# MolunSmartHomeLights_2021-06-01.net
KiCad netlist of a schematic drawn in EasyEDA
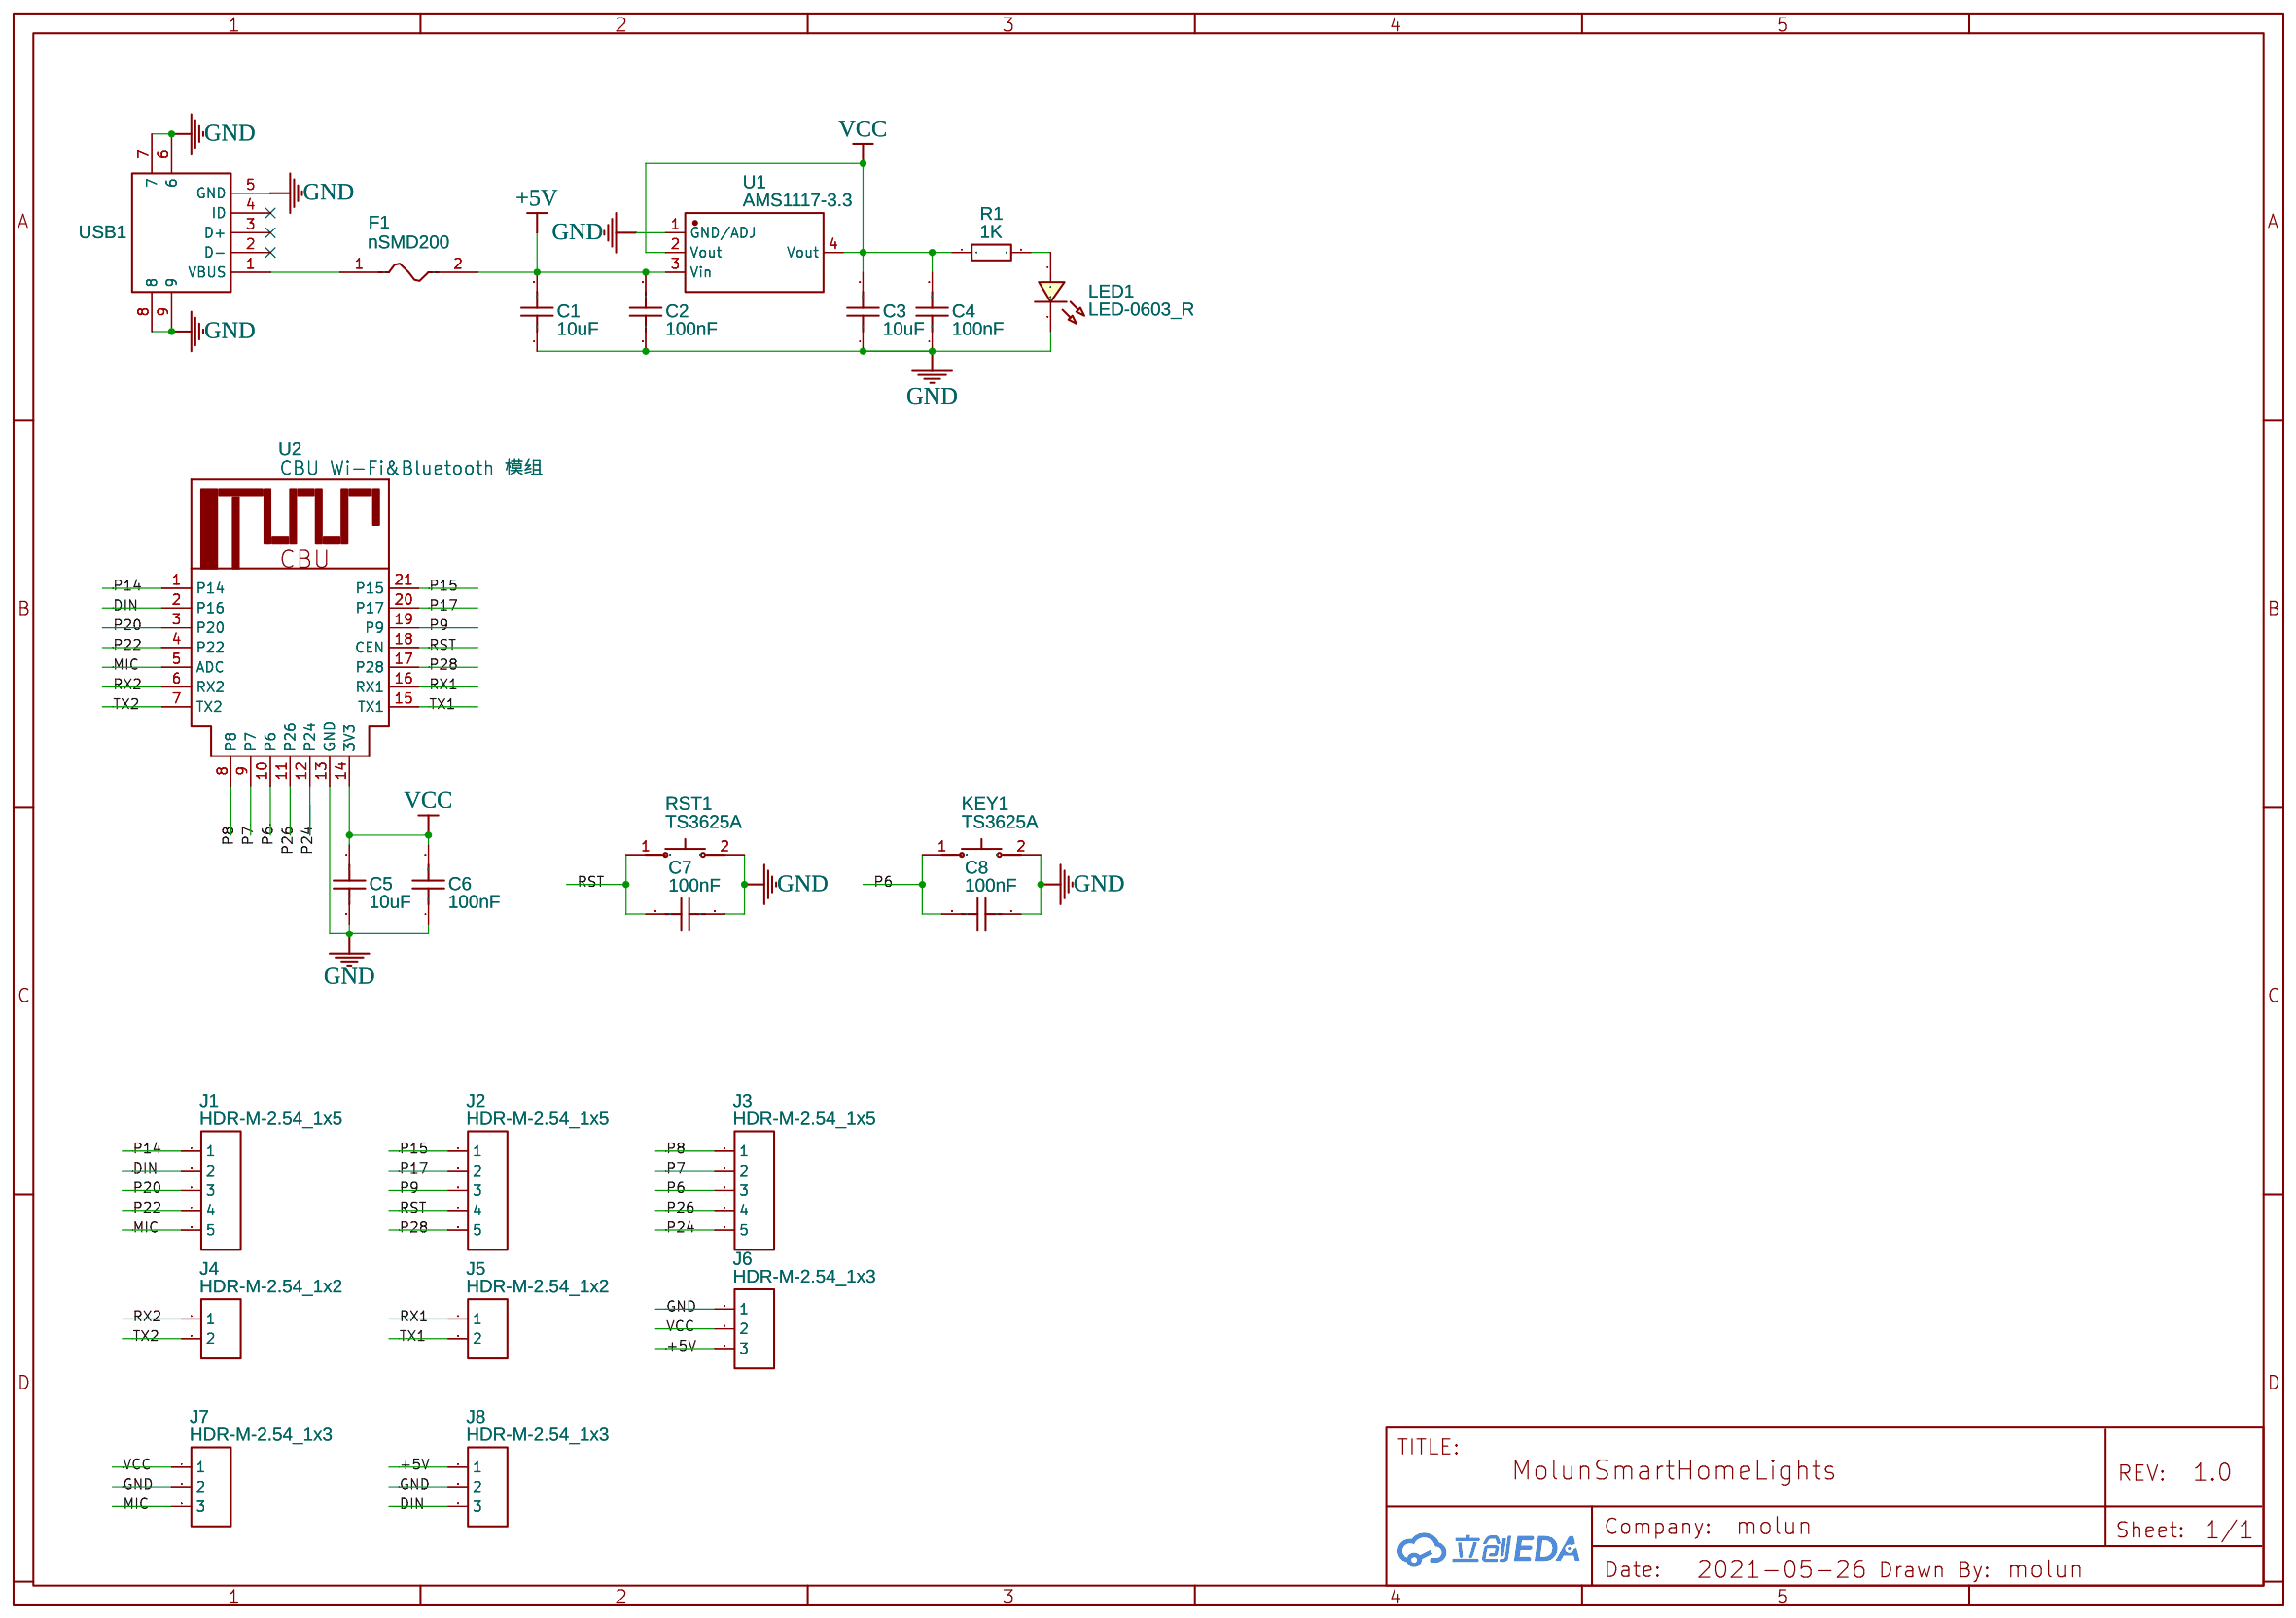
[diagram p0: MolunSmartHomeLights]
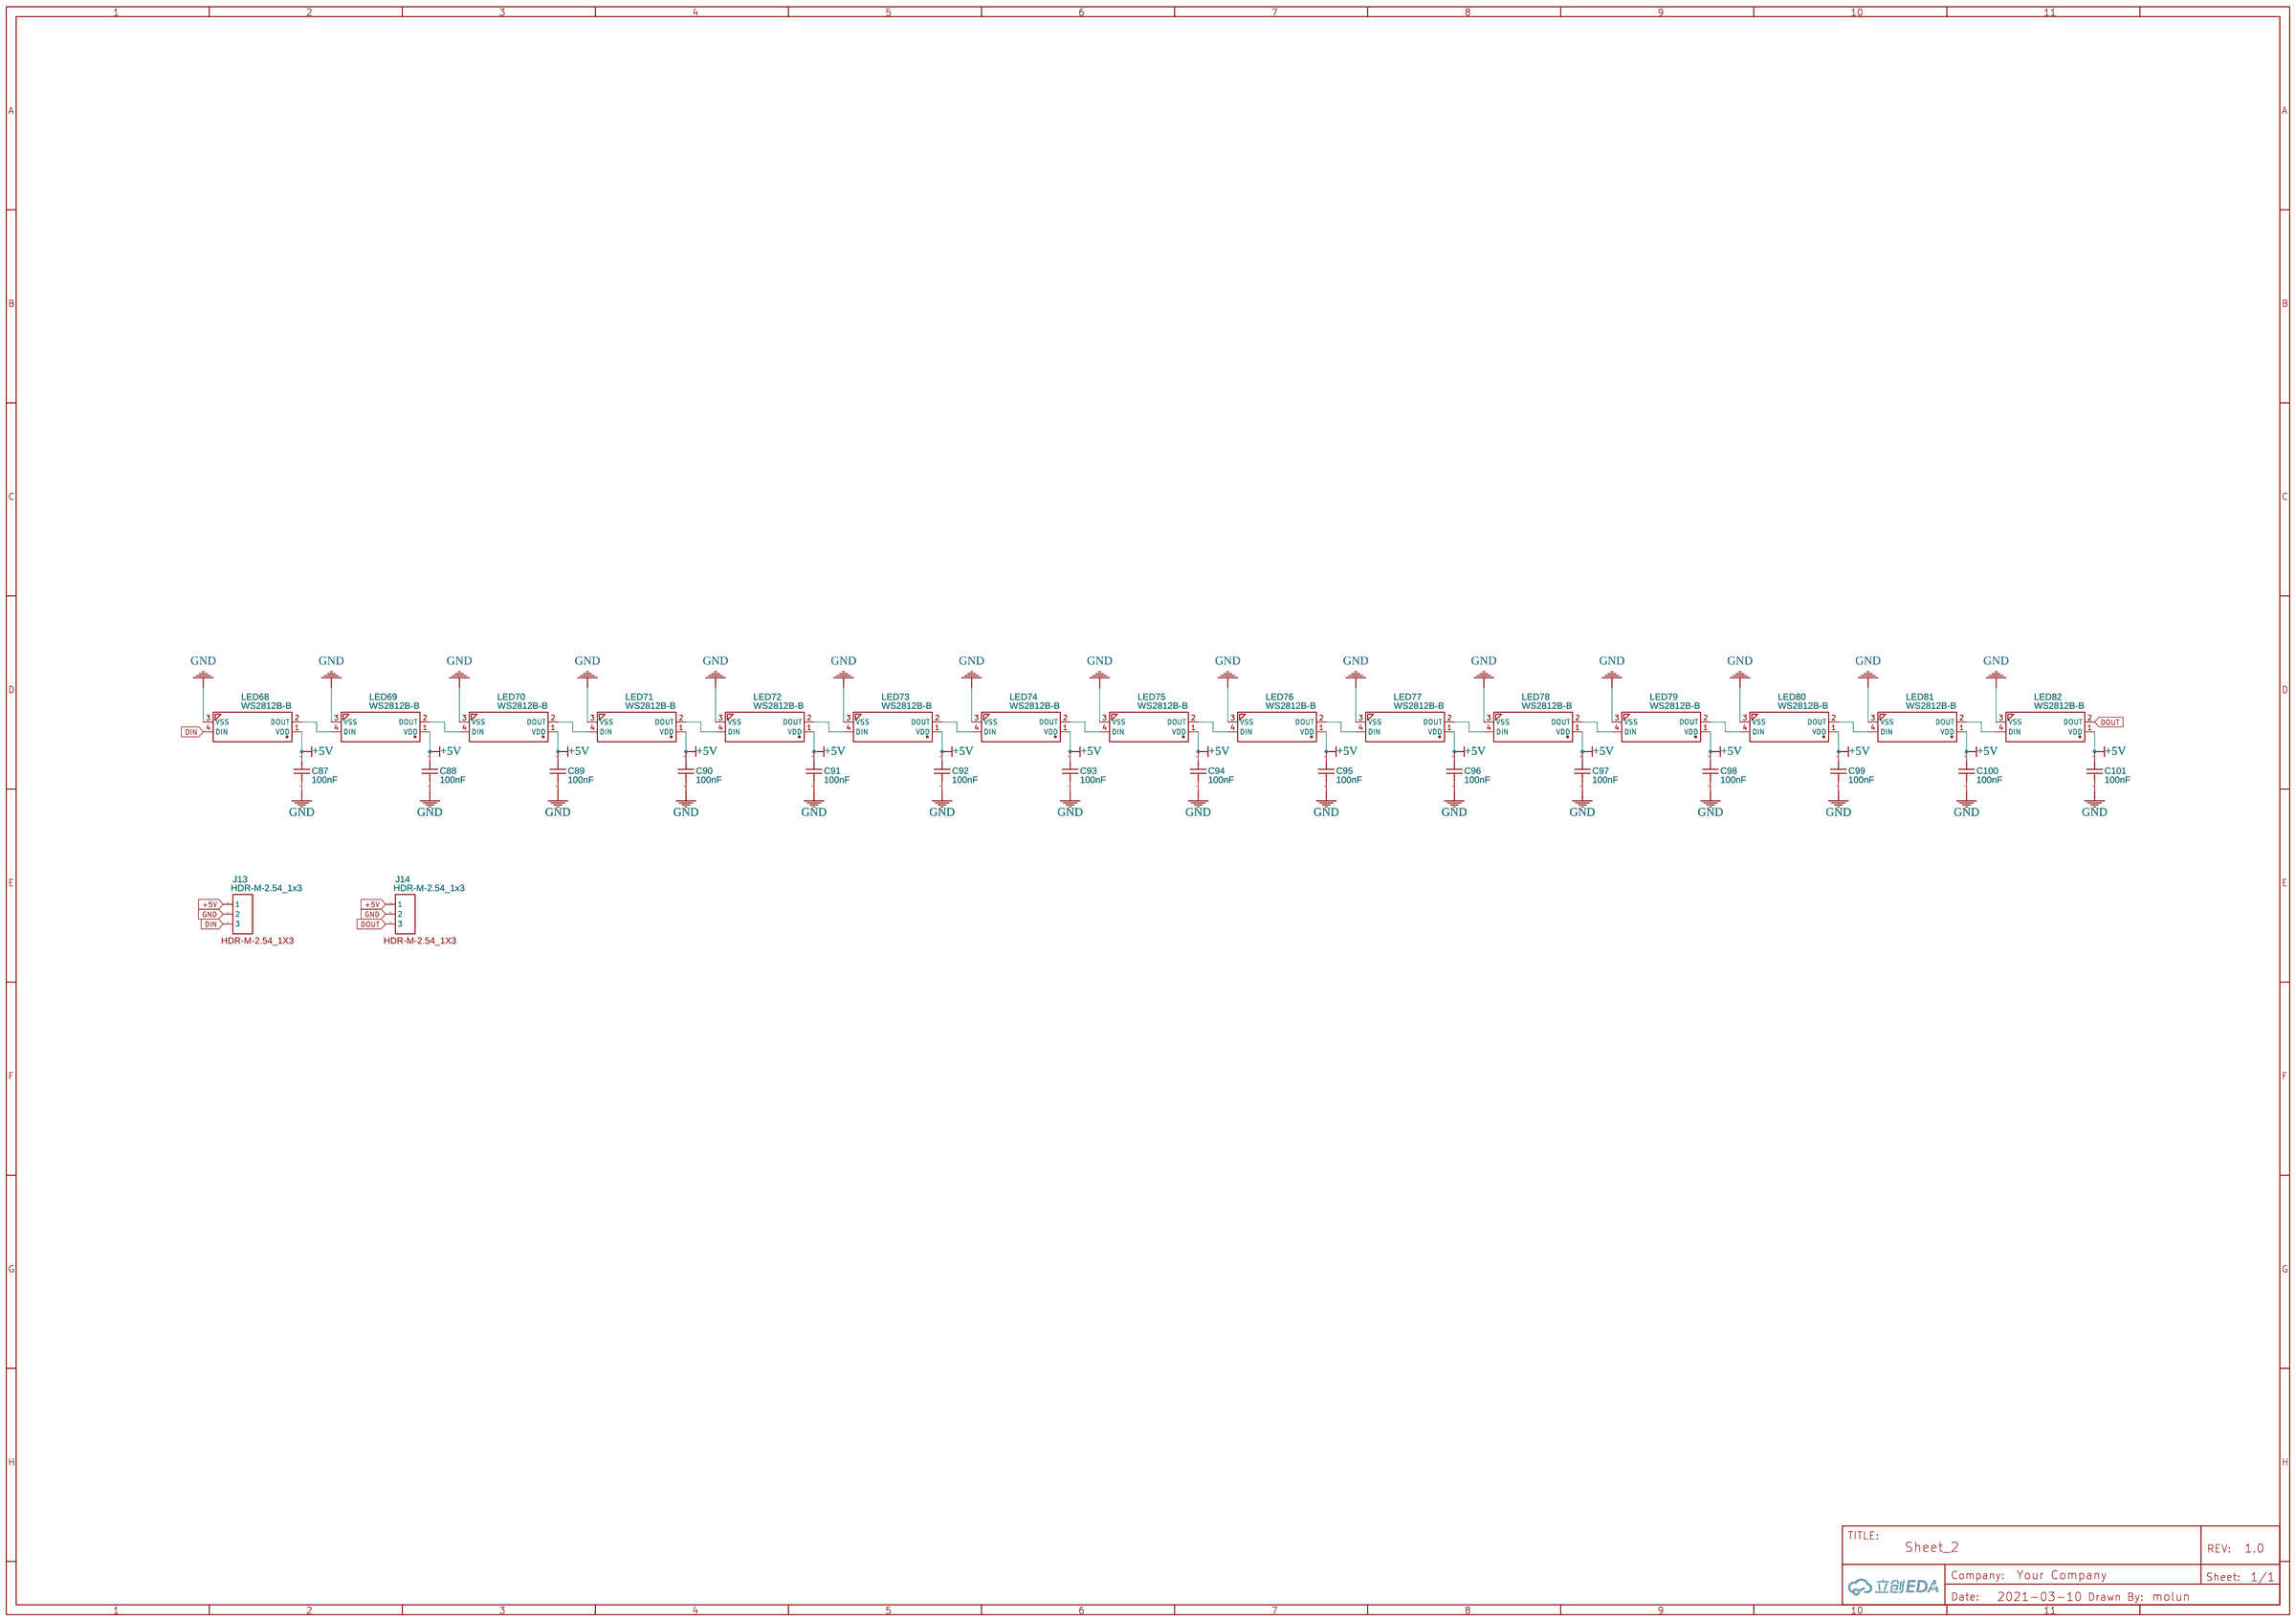
[diagram p1: 4合1 WS2812B圆环灯板]

(export (version "E")
  (design (tool "Eeschema 10.0.6"))
  (components
    (comp (ref "C1")
      (value "10uF")
      (fields
        (field (name "BOM_Manufacturer Part") "CC0603KRX5R6BB106")
        (field (name "BOM_Supplier Part") "C326057")
      )
      (libsource (lib "") (part "CC0603KRX5R6BB106"))
    )
    (comp (ref "C2")
      (value "100nF")
      (fields
        (field (name "BOM_Manufacturer Part") "AC0603KRX7R9BB104")
        (field (name "BOM_Supplier Part") "C149620")
      )
      (libsource (lib "") (part "AC0603KRX7R9BB104"))
    )
    (comp (ref "C3")
      (value "10uF")
      (fields
        (field (name "BOM_Manufacturer Part") "CC0603KRX5R6BB106")
        (field (name "BOM_Supplier Part") "C326057")
      )
      (libsource (lib "") (part "CC0603KRX5R6BB106"))
    )
    (comp (ref "C4")
      (value "100nF")
      (fields
        (field (name "BOM_Manufacturer Part") "AC0603KRX7R9BB104")
        (field (name "BOM_Supplier Part") "C149620")
      )
      (libsource (lib "") (part "AC0603KRX7R9BB104"))
    )
    (comp (ref "C5")
      (value "10uF")
      (fields
        (field (name "BOM_Manufacturer Part") "CL10A106MQ8NNNC")
        (field (name "BOM_Supplier Part") "C1691")
      )
      (libsource (lib "") (part "CL10A106MQ8NNNC"))
    )
    (comp (ref "C6")
      (value "100nF")
      (fields
        (field (name "BOM_Manufacturer Part") "CC0603KRX7R7BB104")
        (field (name "BOM_Supplier Part") "C108079")
      )
      (libsource (lib "") (part "CC0603KRX7R7BB104_1"))
    )
    (comp (ref "C7")
      (value "100nF")
      (fields
        (field (name "BOM_Manufacturer Part") "CC0603KRX7R7BB104")
        (field (name "BOM_Supplier Part") "C108079")
      )
      (libsource (lib "") (part "CC0603KRX7R7BB104"))
    )
    (comp (ref "C8")
      (value "100nF")
      (fields
        (field (name "BOM_Manufacturer Part") "CC0603KRX7R7BB104")
        (field (name "BOM_Supplier Part") "C108079")
      )
      (libsource (lib "") (part "CC0603KRX7R7BB104"))
    )
    (comp (ref "F1")
      (value "nSMD200")
      (fields (field (name "BOM_Supplier Part") "C70085"))
      (libsource (lib "") (part "nSMD200"))
    )
    (comp (ref "J1")
      (value "HDR-M-2.54_1x5")
      (fields (field (name "BOM_Supplier Part") "C358687"))
      (libsource (lib "") (part "HDR-M-2.54_1x5"))
    )
    (comp (ref "J2")
      (value "HDR-M-2.54_1x5")
      (fields (field (name "BOM_Supplier Part") "C358687"))
      (libsource (lib "") (part "HDR-M-2.54_1x5"))
    )
    (comp (ref "J3")
      (value "HDR-M-2.54_1x5")
      (fields (field (name "BOM_Supplier Part") "C358687"))
      (libsource (lib "") (part "HDR-M-2.54_1x5"))
    )
    (comp (ref "J4")
      (value "HDR-M-2.54_1x2")
      (fields (field (name "BOM_Supplier Part") "C124375"))
      (libsource (lib "") (part "HDR-M-2.54_1x2"))
    )
    (comp (ref "J5")
      (value "HDR-M-2.54_1x2")
      (fields (field (name "BOM_Supplier Part") "C124375"))
      (libsource (lib "") (part "HDR-M-2.54_1x2"))
    )
    (comp (ref "J6")
      (value "HDR-M-2.54_1x3")
      (fields (field (name "BOM_Supplier Part") "C180248"))
      (libsource (lib "") (part "HDR-M-2.54_1x3"))
    )
    (comp (ref "J7")
      (value "HDR-M-2.54_1x3")
      (fields (field (name "BOM_Supplier Part") "C180248"))
      (libsource (lib "") (part "HDR-M-2.54_1x3"))
    )
    (comp (ref "J8")
      (value "HDR-M-2.54_1x3")
      (fields (field (name "BOM_Supplier Part") "C180248"))
      (libsource (lib "") (part "HDR-M-2.54_1x3"))
    )
    (comp (ref "KEY1")
      (value "TS3625A")
      (fields (field (name "BOM_Supplier Part") "C398053"))
      (libsource (lib "") (part "TS3625A"))
    )
    (comp (ref "LED1")
      (value "LED-0603_R")
      (fields
        (field (name "BOM_Manufacturer Part") "19-217/R6C-AL1M2VY/3T")
        (field (name "BOM_Supplier Part") "C72044")
      )
      (libsource (lib "") (part "LED-0603_R"))
    )
    (comp (ref "R1")
      (value "1K")
      (fields
        (field (name "BOM_Manufacturer Part") "0603WAF1001T5E")
        (field (name "BOM_Supplier Part") "C21190")
      )
      (libsource (lib "") (part "0603WAF1001T5E"))
    )
    (comp (ref "RST1")
      (value "TS3625A")
      (fields (field (name "BOM_Supplier Part") "C398053"))
      (libsource (lib "") (part "TS3625A_1"))
    )
    (comp (ref "U1")
      (value "AMS1117-3.3")
      (fields (field (name "BOM_Supplier Part") "C6186"))
      (libsource (lib "") (part "AMS1117-3.3"))
    )
    (comp (ref "U2")
      (value "CBU Wi-Fi&Bluetooth 模组")
      (libsource (lib "") (part "CBU Wi-Fi&amp;Bluetooth 模组"))
    )
    (comp (ref "USB1")
      (value "U254-051T-4BH83-F1S")
      (fields (field (name "BOM_Supplier Part") "C397452"))
      (libsource (lib "") (part "U254-051T-4BH83-F1S"))
    )
    (comp (ref "C87")
      (value "100nF")
      (fields
        (field (name "BOM_Manufacturer Part") "CC0603KRX7R7BB104")
        (field (name "BOM_Supplier Part") "C108079")
      )
      (libsource (lib "") (part "CC0603KRX7R7BB104"))
    )
    (comp (ref "C88")
      (value "100nF")
      (fields
        (field (name "BOM_Manufacturer Part") "CC0603KRX7R7BB104")
        (field (name "BOM_Supplier Part") "C108079")
      )
      (libsource (lib "") (part "CC0603KRX7R7BB104"))
    )
    (comp (ref "C89")
      (value "100nF")
      (fields
        (field (name "BOM_Manufacturer Part") "CC0603KRX7R7BB104")
        (field (name "BOM_Supplier Part") "C108079")
      )
      (libsource (lib "") (part "CC0603KRX7R7BB104"))
    )
    (comp (ref "C90")
      (value "100nF")
      (fields
        (field (name "BOM_Manufacturer Part") "CC0603KRX7R7BB104")
        (field (name "BOM_Supplier Part") "C108079")
      )
      (libsource (lib "") (part "CC0603KRX7R7BB104"))
    )
    (comp (ref "C91")
      (value "100nF")
      (fields
        (field (name "BOM_Manufacturer Part") "CC0603KRX7R7BB104")
        (field (name "BOM_Supplier Part") "C108079")
      )
      (libsource (lib "") (part "CC0603KRX7R7BB104"))
    )
    (comp (ref "C92")
      (value "100nF")
      (fields
        (field (name "BOM_Manufacturer Part") "CC0603KRX7R7BB104")
        (field (name "BOM_Supplier Part") "C108079")
      )
      (libsource (lib "") (part "CC0603KRX7R7BB104"))
    )
    (comp (ref "C93")
      (value "100nF")
      (fields
        (field (name "BOM_Manufacturer Part") "CC0603KRX7R7BB104")
        (field (name "BOM_Supplier Part") "C108079")
      )
      (libsource (lib "") (part "CC0603KRX7R7BB104"))
    )
    (comp (ref "C94")
      (value "100nF")
      (fields
        (field (name "BOM_Manufacturer Part") "CC0603KRX7R7BB104")
        (field (name "BOM_Supplier Part") "C108079")
      )
      (libsource (lib "") (part "CC0603KRX7R7BB104"))
    )
    (comp (ref "C95")
      (value "100nF")
      (fields
        (field (name "BOM_Manufacturer Part") "CC0603KRX7R7BB104")
        (field (name "BOM_Supplier Part") "C108079")
      )
      (libsource (lib "") (part "CC0603KRX7R7BB104"))
    )
    (comp (ref "C96")
      (value "100nF")
      (fields
        (field (name "BOM_Manufacturer Part") "CC0603KRX7R7BB104")
        (field (name "BOM_Supplier Part") "C108079")
      )
      (libsource (lib "") (part "CC0603KRX7R7BB104"))
    )
    (comp (ref "C97")
      (value "100nF")
      (fields
        (field (name "BOM_Manufacturer Part") "CC0603KRX7R7BB104")
        (field (name "BOM_Supplier Part") "C108079")
      )
      (libsource (lib "") (part "CC0603KRX7R7BB104"))
    )
    (comp (ref "C98")
      (value "100nF")
      (fields
        (field (name "BOM_Manufacturer Part") "CC0603KRX7R7BB104")
        (field (name "BOM_Supplier Part") "C108079")
      )
      (libsource (lib "") (part "CC0603KRX7R7BB104"))
    )
    (comp (ref "C99")
      (value "100nF")
      (fields
        (field (name "BOM_Manufacturer Part") "CC0603KRX7R7BB104")
        (field (name "BOM_Supplier Part") "C108079")
      )
      (libsource (lib "") (part "CC0603KRX7R7BB104"))
    )
    (comp (ref "C100")
      (value "100nF")
      (fields
        (field (name "BOM_Manufacturer Part") "CC0603KRX7R7BB104")
        (field (name "BOM_Supplier Part") "C108079")
      )
      (libsource (lib "") (part "CC0603KRX7R7BB104"))
    )
    (comp (ref "C101")
      (value "100nF")
      (fields
        (field (name "BOM_Manufacturer Part") "CC0603KRX7R7BB104")
        (field (name "BOM_Supplier Part") "C108079")
      )
      (libsource (lib "") (part "CC0603KRX7R7BB104"))
    )
    (comp (ref "J13")
      (value "HDR-M-2.54_1x3")
      (fields (field (name "BOM_Supplier Part") "C180248"))
      (libsource (lib "") (part "HDR-M-2.54_1x3"))
    )
    (comp (ref "J14")
      (value "HDR-M-2.54_1x3")
      (fields (field (name "BOM_Supplier Part") "C180248"))
      (libsource (lib "") (part "HDR-M-2.54_1x3"))
    )
    (comp (ref "LED68")
      (value "WS2812B-B")
      (fields (field (name "BOM_Supplier Part") "C114586"))
      (libsource (lib "") (part "WS2812B-B"))
    )
    (comp (ref "LED69")
      (value "WS2812B-B")
      (fields (field (name "BOM_Supplier Part") "C114586"))
      (libsource (lib "") (part "WS2812B-B"))
    )
    (comp (ref "LED70")
      (value "WS2812B-B")
      (fields (field (name "BOM_Supplier Part") "C114586"))
      (libsource (lib "") (part "WS2812B-B"))
    )
    (comp (ref "LED71")
      (value "WS2812B-B")
      (fields (field (name "BOM_Supplier Part") "C114586"))
      (libsource (lib "") (part "WS2812B-B"))
    )
    (comp (ref "LED72")
      (value "WS2812B-B")
      (fields (field (name "BOM_Supplier Part") "C114586"))
      (libsource (lib "") (part "WS2812B-B"))
    )
    (comp (ref "LED73")
      (value "WS2812B-B")
      (fields (field (name "BOM_Supplier Part") "C114586"))
      (libsource (lib "") (part "WS2812B-B"))
    )
    (comp (ref "LED74")
      (value "WS2812B-B")
      (fields (field (name "BOM_Supplier Part") "C114586"))
      (libsource (lib "") (part "WS2812B-B"))
    )
    (comp (ref "LED75")
      (value "WS2812B-B")
      (fields (field (name "BOM_Supplier Part") "C114586"))
      (libsource (lib "") (part "WS2812B-B"))
    )
    (comp (ref "LED76")
      (value "WS2812B-B")
      (fields (field (name "BOM_Supplier Part") "C114586"))
      (libsource (lib "") (part "WS2812B-B"))
    )
    (comp (ref "LED77")
      (value "WS2812B-B")
      (fields (field (name "BOM_Supplier Part") "C114586"))
      (libsource (lib "") (part "WS2812B-B"))
    )
    (comp (ref "LED78")
      (value "WS2812B-B")
      (fields (field (name "BOM_Supplier Part") "C114586"))
      (libsource (lib "") (part "WS2812B-B"))
    )
    (comp (ref "LED79")
      (value "WS2812B-B")
      (fields (field (name "BOM_Supplier Part") "C114586"))
      (libsource (lib "") (part "WS2812B-B"))
    )
    (comp (ref "LED80")
      (value "WS2812B-B")
      (fields (field (name "BOM_Supplier Part") "C114586"))
      (libsource (lib "") (part "WS2812B-B"))
    )
    (comp (ref "LED81")
      (value "WS2812B-B")
      (fields (field (name "BOM_Supplier Part") "C114586"))
      (libsource (lib "") (part "WS2812B-B"))
    )
    (comp (ref "LED82")
      (value "WS2812B-B")
      (fields (field (name "BOM_Supplier Part") "C114586"))
      (libsource (lib "") (part "WS2812B-B"))
    )
  )
  (nets
    (net (code "1") (name "+5V") (class "Default")
      (node (ref "C1") (pin "2") (pinfunction "2_2") (pintype "unspecified"))
      (node (ref "C100") (pin "2") (pinfunction "2_2") (pintype "unspecified"))
      (node (ref "C101") (pin "2") (pinfunction "2_2") (pintype "unspecified"))
      (node (ref "C2") (pin "2") (pinfunction "2_2") (pintype "unspecified"))
      (node (ref "C87") (pin "2") (pinfunction "2_2") (pintype "unspecified"))
      (node (ref "C88") (pin "2") (pinfunction "2_2") (pintype "unspecified"))
      (node (ref "C89") (pin "2") (pinfunction "2_2") (pintype "unspecified"))
      (node (ref "C90") (pin "2") (pinfunction "2_2") (pintype "unspecified"))
      (node (ref "C91") (pin "2") (pinfunction "2_2") (pintype "unspecified"))
      (node (ref "C92") (pin "2") (pinfunction "2_2") (pintype "unspecified"))
      (node (ref "C93") (pin "2") (pinfunction "2_2") (pintype "unspecified"))
      (node (ref "C94") (pin "2") (pinfunction "2_2") (pintype "unspecified"))
      (node (ref "C95") (pin "2") (pinfunction "2_2") (pintype "unspecified"))
      (node (ref "C96") (pin "2") (pinfunction "2_2") (pintype "unspecified"))
      (node (ref "C97") (pin "2") (pinfunction "2_2") (pintype "unspecified"))
      (node (ref "C98") (pin "2") (pinfunction "2_2") (pintype "unspecified"))
      (node (ref "C99") (pin "2") (pinfunction "2_2") (pintype "unspecified"))
      (node (ref "F1") (pin "2") (pinfunction "2_2") (pintype "unspecified"))
      (node (ref "J13") (pin "1") (pinfunction "1_1") (pintype "input"))
      (node (ref "J14") (pin "1") (pinfunction "1_1") (pintype "input"))
      (node (ref "J6") (pin "3") (pinfunction "3_3") (pintype "input"))
      (node (ref "J8") (pin "1") (pinfunction "1_1") (pintype "input"))
      (node (ref "LED68") (pin "1") (pinfunction "VDD_1") (pintype "unspecified"))
      (node (ref "LED69") (pin "1") (pinfunction "VDD_1") (pintype "unspecified"))
      (node (ref "LED70") (pin "1") (pinfunction "VDD_1") (pintype "unspecified"))
      (node (ref "LED71") (pin "1") (pinfunction "VDD_1") (pintype "unspecified"))
      (node (ref "LED72") (pin "1") (pinfunction "VDD_1") (pintype "unspecified"))
      (node (ref "LED73") (pin "1") (pinfunction "VDD_1") (pintype "unspecified"))
      (node (ref "LED74") (pin "1") (pinfunction "VDD_1") (pintype "unspecified"))
      (node (ref "LED75") (pin "1") (pinfunction "VDD_1") (pintype "unspecified"))
      (node (ref "LED76") (pin "1") (pinfunction "VDD_1") (pintype "unspecified"))
      (node (ref "LED77") (pin "1") (pinfunction "VDD_1") (pintype "unspecified"))
      (node (ref "LED78") (pin "1") (pinfunction "VDD_1") (pintype "unspecified"))
      (node (ref "LED79") (pin "1") (pinfunction "VDD_1") (pintype "unspecified"))
      (node (ref "LED80") (pin "1") (pinfunction "VDD_1") (pintype "unspecified"))
      (node (ref "LED81") (pin "1") (pinfunction "VDD_1") (pintype "unspecified"))
      (node (ref "LED82") (pin "1") (pinfunction "VDD_1") (pintype "unspecified"))
      (node (ref "U1") (pin "3") (pinfunction "Vin_3") (pintype "unspecified"))
    )
    (net (code "2") (name "DIN") (class "Default")
      (node (ref "J1") (pin "2") (pinfunction "2_2") (pintype "unspecified"))
      (node (ref "J13") (pin "3") (pinfunction "3_3") (pintype "input"))
      (node (ref "J8") (pin "3") (pinfunction "3_3") (pintype "input"))
      (node (ref "LED68") (pin "4") (pinfunction "DIN_4") (pintype "unspecified"))
      (node (ref "U2") (pin "2") (pinfunction "P16_2") (pintype "bidirectional"))
    )
    (net (code "3") (name "DOUT") (class "Default")
      (node (ref "J14") (pin "3") (pinfunction "3_3") (pintype "input"))
      (node (ref "LED82") (pin "2") (pinfunction "DOUT_2") (pintype "unspecified"))
    )
    (net (code "4") (name "GND") (class "Default")
      (node (ref "C1") (pin "1") (pinfunction "1_1") (pintype "unspecified"))
      (node (ref "C100") (pin "1") (pinfunction "1_1") (pintype "unspecified"))
      (node (ref "C101") (pin "1") (pinfunction "1_1") (pintype "unspecified"))
      (node (ref "C2") (pin "1") (pinfunction "1_1") (pintype "unspecified"))
      (node (ref "C3") (pin "1") (pinfunction "1_1") (pintype "unspecified"))
      (node (ref "C4") (pin "1") (pinfunction "1_1") (pintype "unspecified"))
      (node (ref "C5") (pin "2") (pinfunction "2_2") (pintype "unspecified"))
      (node (ref "C6") (pin "1") (pinfunction "1_1") (pintype "unspecified"))
      (node (ref "C7") (pin "1") (pinfunction "1_1") (pintype "unspecified"))
      (node (ref "C8") (pin "1") (pinfunction "1_1") (pintype "unspecified"))
      (node (ref "C87") (pin "1") (pinfunction "1_1") (pintype "unspecified"))
      (node (ref "C88") (pin "1") (pinfunction "1_1") (pintype "unspecified"))
      (node (ref "C89") (pin "1") (pinfunction "1_1") (pintype "unspecified"))
      (node (ref "C90") (pin "1") (pinfunction "1_1") (pintype "unspecified"))
      (node (ref "C91") (pin "1") (pinfunction "1_1") (pintype "unspecified"))
      (node (ref "C92") (pin "1") (pinfunction "1_1") (pintype "unspecified"))
      (node (ref "C93") (pin "1") (pinfunction "1_1") (pintype "unspecified"))
      (node (ref "C94") (pin "1") (pinfunction "1_1") (pintype "unspecified"))
      (node (ref "C95") (pin "1") (pinfunction "1_1") (pintype "unspecified"))
      (node (ref "C96") (pin "1") (pinfunction "1_1") (pintype "unspecified"))
      (node (ref "C97") (pin "1") (pinfunction "1_1") (pintype "unspecified"))
      (node (ref "C98") (pin "1") (pinfunction "1_1") (pintype "unspecified"))
      (node (ref "C99") (pin "1") (pinfunction "1_1") (pintype "unspecified"))
      (node (ref "J13") (pin "2") (pinfunction "2_2") (pintype "input"))
      (node (ref "J14") (pin "2") (pinfunction "2_2") (pintype "input"))
      (node (ref "J6") (pin "1") (pinfunction "1_1") (pintype "input"))
      (node (ref "J7") (pin "2") (pinfunction "2_2") (pintype "input"))
      (node (ref "J8") (pin "2") (pinfunction "2_2") (pintype "input"))
      (node (ref "KEY1") (pin "2") (pinfunction "2_2") (pintype "unspecified"))
      (node (ref "LED1") (pin "2") (pinfunction "2_2") (pintype "unspecified"))
      (node (ref "LED68") (pin "3") (pinfunction "VSS_3") (pintype "unspecified"))
      (node (ref "LED69") (pin "3") (pinfunction "VSS_3") (pintype "unspecified"))
      (node (ref "LED70") (pin "3") (pinfunction "VSS_3") (pintype "unspecified"))
      (node (ref "LED71") (pin "3") (pinfunction "VSS_3") (pintype "unspecified"))
      (node (ref "LED72") (pin "3") (pinfunction "VSS_3") (pintype "unspecified"))
      (node (ref "LED73") (pin "3") (pinfunction "VSS_3") (pintype "unspecified"))
      (node (ref "LED74") (pin "3") (pinfunction "VSS_3") (pintype "unspecified"))
      (node (ref "LED75") (pin "3") (pinfunction "VSS_3") (pintype "unspecified"))
      (node (ref "LED76") (pin "3") (pinfunction "VSS_3") (pintype "unspecified"))
      (node (ref "LED77") (pin "3") (pinfunction "VSS_3") (pintype "unspecified"))
      (node (ref "LED78") (pin "3") (pinfunction "VSS_3") (pintype "unspecified"))
      (node (ref "LED79") (pin "3") (pinfunction "VSS_3") (pintype "unspecified"))
      (node (ref "LED80") (pin "3") (pinfunction "VSS_3") (pintype "unspecified"))
      (node (ref "LED81") (pin "3") (pinfunction "VSS_3") (pintype "unspecified"))
      (node (ref "LED82") (pin "3") (pinfunction "VSS_3") (pintype "unspecified"))
      (node (ref "RST1") (pin "2") (pinfunction "2_2") (pintype "unspecified"))
      (node (ref "U1") (pin "1") (pinfunction "GND/ADJ_1") (pintype "unspecified"))
      (node (ref "U2") (pin "13") (pinfunction "GND_13") (pintype "passive"))
      (node (ref "USB1") (pin "5") (pinfunction "GND_5") (pintype "unspecified"))
      (node (ref "USB1") (pin "6") (pinfunction "6_6") (pintype "unspecified"))
      (node (ref "USB1") (pin "7") (pinfunction "7_7") (pintype "unspecified"))
      (node (ref "USB1") (pin "8") (pinfunction "8_8") (pintype "unspecified"))
      (node (ref "USB1") (pin "9") (pinfunction "9_9") (pintype "unspecified"))
    )
    (net (code "5") (name "MIC") (class "Default")
      (node (ref "J1") (pin "5") (pinfunction "5_5") (pintype "unspecified"))
      (node (ref "J7") (pin "3") (pinfunction "3_3") (pintype "input"))
      (node (ref "U2") (pin "5") (pinfunction "ADC_5") (pintype "bidirectional"))
    )
    (net (code "6") (name "Net-(LED1-Pad1)") (class "Default")
      (node (ref "LED1") (pin "1") (pinfunction "1_1") (pintype "unspecified"))
      (node (ref "R1") (pin "2") (pinfunction "2_2") (pintype "input"))
    )
    (net (code "7") (name "Net-(LED68-DOUT)") (class "Default")
      (node (ref "LED68") (pin "2") (pinfunction "DOUT_2") (pintype "unspecified"))
      (node (ref "LED69") (pin "4") (pinfunction "DIN_4") (pintype "unspecified"))
    )
    (net (code "8") (name "Net-(LED69-DOUT)") (class "Default")
      (node (ref "LED69") (pin "2") (pinfunction "DOUT_2") (pintype "unspecified"))
      (node (ref "LED70") (pin "4") (pinfunction "DIN_4") (pintype "unspecified"))
    )
    (net (code "9") (name "Net-(LED70-DOUT)") (class "Default")
      (node (ref "LED70") (pin "2") (pinfunction "DOUT_2") (pintype "unspecified"))
      (node (ref "LED71") (pin "4") (pinfunction "DIN_4") (pintype "unspecified"))
    )
    (net (code "10") (name "Net-(LED71-DOUT)") (class "Default")
      (node (ref "LED71") (pin "2") (pinfunction "DOUT_2") (pintype "unspecified"))
      (node (ref "LED72") (pin "4") (pinfunction "DIN_4") (pintype "unspecified"))
    )
    (net (code "11") (name "Net-(LED72-DOUT)") (class "Default")
      (node (ref "LED72") (pin "2") (pinfunction "DOUT_2") (pintype "unspecified"))
      (node (ref "LED73") (pin "4") (pinfunction "DIN_4") (pintype "unspecified"))
    )
    (net (code "12") (name "Net-(LED73-DOUT)") (class "Default")
      (node (ref "LED73") (pin "2") (pinfunction "DOUT_2") (pintype "unspecified"))
      (node (ref "LED74") (pin "4") (pinfunction "DIN_4") (pintype "unspecified"))
    )
    (net (code "13") (name "Net-(LED74-DOUT)") (class "Default")
      (node (ref "LED74") (pin "2") (pinfunction "DOUT_2") (pintype "unspecified"))
      (node (ref "LED75") (pin "4") (pinfunction "DIN_4") (pintype "unspecified"))
    )
    (net (code "14") (name "Net-(LED75-DOUT)") (class "Default")
      (node (ref "LED75") (pin "2") (pinfunction "DOUT_2") (pintype "unspecified"))
      (node (ref "LED76") (pin "4") (pinfunction "DIN_4") (pintype "unspecified"))
    )
    (net (code "15") (name "Net-(LED76-DOUT)") (class "Default")
      (node (ref "LED76") (pin "2") (pinfunction "DOUT_2") (pintype "unspecified"))
      (node (ref "LED77") (pin "4") (pinfunction "DIN_4") (pintype "unspecified"))
    )
    (net (code "16") (name "Net-(LED77-DOUT)") (class "Default")
      (node (ref "LED77") (pin "2") (pinfunction "DOUT_2") (pintype "unspecified"))
      (node (ref "LED78") (pin "4") (pinfunction "DIN_4") (pintype "unspecified"))
    )
    (net (code "17") (name "Net-(LED78-DOUT)") (class "Default")
      (node (ref "LED78") (pin "2") (pinfunction "DOUT_2") (pintype "unspecified"))
      (node (ref "LED79") (pin "4") (pinfunction "DIN_4") (pintype "unspecified"))
    )
    (net (code "18") (name "Net-(LED79-DOUT)") (class "Default")
      (node (ref "LED79") (pin "2") (pinfunction "DOUT_2") (pintype "unspecified"))
      (node (ref "LED80") (pin "4") (pinfunction "DIN_4") (pintype "unspecified"))
    )
    (net (code "19") (name "Net-(LED80-DOUT)") (class "Default")
      (node (ref "LED80") (pin "2") (pinfunction "DOUT_2") (pintype "unspecified"))
      (node (ref "LED81") (pin "4") (pinfunction "DIN_4") (pintype "unspecified"))
    )
    (net (code "20") (name "Net-(LED81-DOUT)") (class "Default")
      (node (ref "LED81") (pin "2") (pinfunction "DOUT_2") (pintype "unspecified"))
      (node (ref "LED82") (pin "4") (pinfunction "DIN_4") (pintype "unspecified"))
    )
    (net (code "21") (name "Net-(USB1-VBUS)") (class "Default")
      (node (ref "F1") (pin "1") (pinfunction "1_1") (pintype "unspecified"))
      (node (ref "USB1") (pin "1") (pinfunction "VBUS_1") (pintype "unspecified"))
    )
    (net (code "22") (name "P6") (class "Default")
      (node (ref "C8") (pin "2") (pinfunction "2_2") (pintype "unspecified"))
      (node (ref "J3") (pin "3") (pinfunction "3_3") (pintype "unspecified"))
      (node (ref "KEY1") (pin "1") (pinfunction "1_1") (pintype "unspecified"))
      (node (ref "U2") (pin "10") (pinfunction "P6_10") (pintype "bidirectional"))
    )
    (net (code "23") (name "P7") (class "Default")
      (node (ref "J3") (pin "2") (pinfunction "2_2") (pintype "unspecified"))
      (node (ref "U2") (pin "9") (pinfunction "P7_9") (pintype "bidirectional"))
    )
    (net (code "24") (name "P8") (class "Default")
      (node (ref "J3") (pin "1") (pinfunction "1_1") (pintype "unspecified"))
      (node (ref "U2") (pin "8") (pinfunction "P8_8") (pintype "bidirectional"))
    )
    (net (code "25") (name "P9") (class "Default")
      (node (ref "J2") (pin "3") (pinfunction "3_3") (pintype "unspecified"))
      (node (ref "U2") (pin "19") (pinfunction "P9_19") (pintype "bidirectional"))
    )
    (net (code "26") (name "P14") (class "Default")
      (node (ref "J1") (pin "1") (pinfunction "1_1") (pintype "unspecified"))
      (node (ref "U2") (pin "1") (pinfunction "P14_1") (pintype "bidirectional"))
    )
    (net (code "27") (name "P15") (class "Default")
      (node (ref "J2") (pin "1") (pinfunction "1_1") (pintype "unspecified"))
      (node (ref "U2") (pin "21") (pinfunction "P15_21") (pintype "bidirectional"))
    )
    (net (code "28") (name "P17") (class "Default")
      (node (ref "J2") (pin "2") (pinfunction "2_2") (pintype "unspecified"))
      (node (ref "U2") (pin "20") (pinfunction "P17_20") (pintype "bidirectional"))
    )
    (net (code "29") (name "P20") (class "Default")
      (node (ref "J1") (pin "3") (pinfunction "3_3") (pintype "unspecified"))
      (node (ref "U2") (pin "3") (pinfunction "P20_3") (pintype "bidirectional"))
    )
    (net (code "30") (name "P22") (class "Default")
      (node (ref "J1") (pin "4") (pinfunction "4_4") (pintype "unspecified"))
      (node (ref "U2") (pin "4") (pinfunction "P22_4") (pintype "bidirectional"))
    )
    (net (code "31") (name "P24") (class "Default")
      (node (ref "J3") (pin "5") (pinfunction "5_5") (pintype "unspecified"))
      (node (ref "U2") (pin "12") (pinfunction "P24_12") (pintype "bidirectional"))
    )
    (net (code "32") (name "P26") (class "Default")
      (node (ref "J3") (pin "4") (pinfunction "4_4") (pintype "unspecified"))
      (node (ref "U2") (pin "11") (pinfunction "P26_11") (pintype "bidirectional"))
    )
    (net (code "33") (name "P28") (class "Default")
      (node (ref "J2") (pin "5") (pinfunction "5_5") (pintype "unspecified"))
      (node (ref "U2") (pin "17") (pinfunction "P28_17") (pintype "bidirectional"))
    )
    (net (code "34") (name "RST") (class "Default")
      (node (ref "C7") (pin "2") (pinfunction "2_2") (pintype "unspecified"))
      (node (ref "J2") (pin "4") (pinfunction "4_4") (pintype "unspecified"))
      (node (ref "RST1") (pin "1") (pinfunction "1_1") (pintype "unspecified"))
      (node (ref "U2") (pin "18") (pinfunction "CEN_18") (pintype "bidirectional"))
    )
    (net (code "35") (name "RX1") (class "Default")
      (node (ref "J5") (pin "1") (pinfunction "1_1") (pintype "unspecified"))
      (node (ref "U2") (pin "16") (pinfunction "RX1_16") (pintype "bidirectional"))
    )
    (net (code "36") (name "RX2") (class "Default")
      (node (ref "J4") (pin "1") (pinfunction "1_1") (pintype "unspecified"))
      (node (ref "U2") (pin "6") (pinfunction "RX2_6") (pintype "bidirectional"))
    )
    (net (code "37") (name "TX1") (class "Default")
      (node (ref "J5") (pin "2") (pinfunction "2_2") (pintype "unspecified"))
      (node (ref "U2") (pin "15") (pinfunction "TX1_15") (pintype "bidirectional"))
    )
    (net (code "38") (name "TX2") (class "Default")
      (node (ref "J4") (pin "2") (pinfunction "2_2") (pintype "unspecified"))
      (node (ref "U2") (pin "7") (pinfunction "TX2_7") (pintype "bidirectional"))
    )
    (net (code "39") (name "VCC") (class "Default")
      (node (ref "C3") (pin "2") (pinfunction "2_2") (pintype "unspecified"))
      (node (ref "C4") (pin "2") (pinfunction "2_2") (pintype "unspecified"))
      (node (ref "C5") (pin "1") (pinfunction "1_1") (pintype "unspecified"))
      (node (ref "C6") (pin "2") (pinfunction "2_2") (pintype "unspecified"))
      (node (ref "J6") (pin "2") (pinfunction "2_2") (pintype "input"))
      (node (ref "J7") (pin "1") (pinfunction "1_1") (pintype "input"))
      (node (ref "R1") (pin "1") (pinfunction "1_1") (pintype "input"))
      (node (ref "U1") (pin "2") (pinfunction "Vout_2") (pintype "unspecified"))
      (node (ref "U1") (pin "4") (pinfunction "Vout_4") (pintype "unspecified"))
      (node (ref "U2") (pin "14") (pinfunction "3V3_14") (pintype "passive"))
    )
    (net (code "40") (name "unconnected-(USB1-D+-Pad3)") (class "Default")
      (node (ref "USB1") (pin "3") (pinfunction "D+_3") (pintype "unspecified+no_connect"))
    )
    (net (code "41") (name "unconnected-(USB1-D--Pad2)") (class "Default")
      (node (ref "USB1") (pin "2") (pinfunction "D-_2") (pintype "unspecified+no_connect"))
    )
    (net (code "42") (name "unconnected-(USB1-ID-Pad4)") (class "Default")
      (node (ref "USB1") (pin "4") (pinfunction "ID_4") (pintype "unspecified+no_connect"))
    )
  )
)
